# RasPiDV.net
KiCad netlist of a schematic drawn in EAGLE
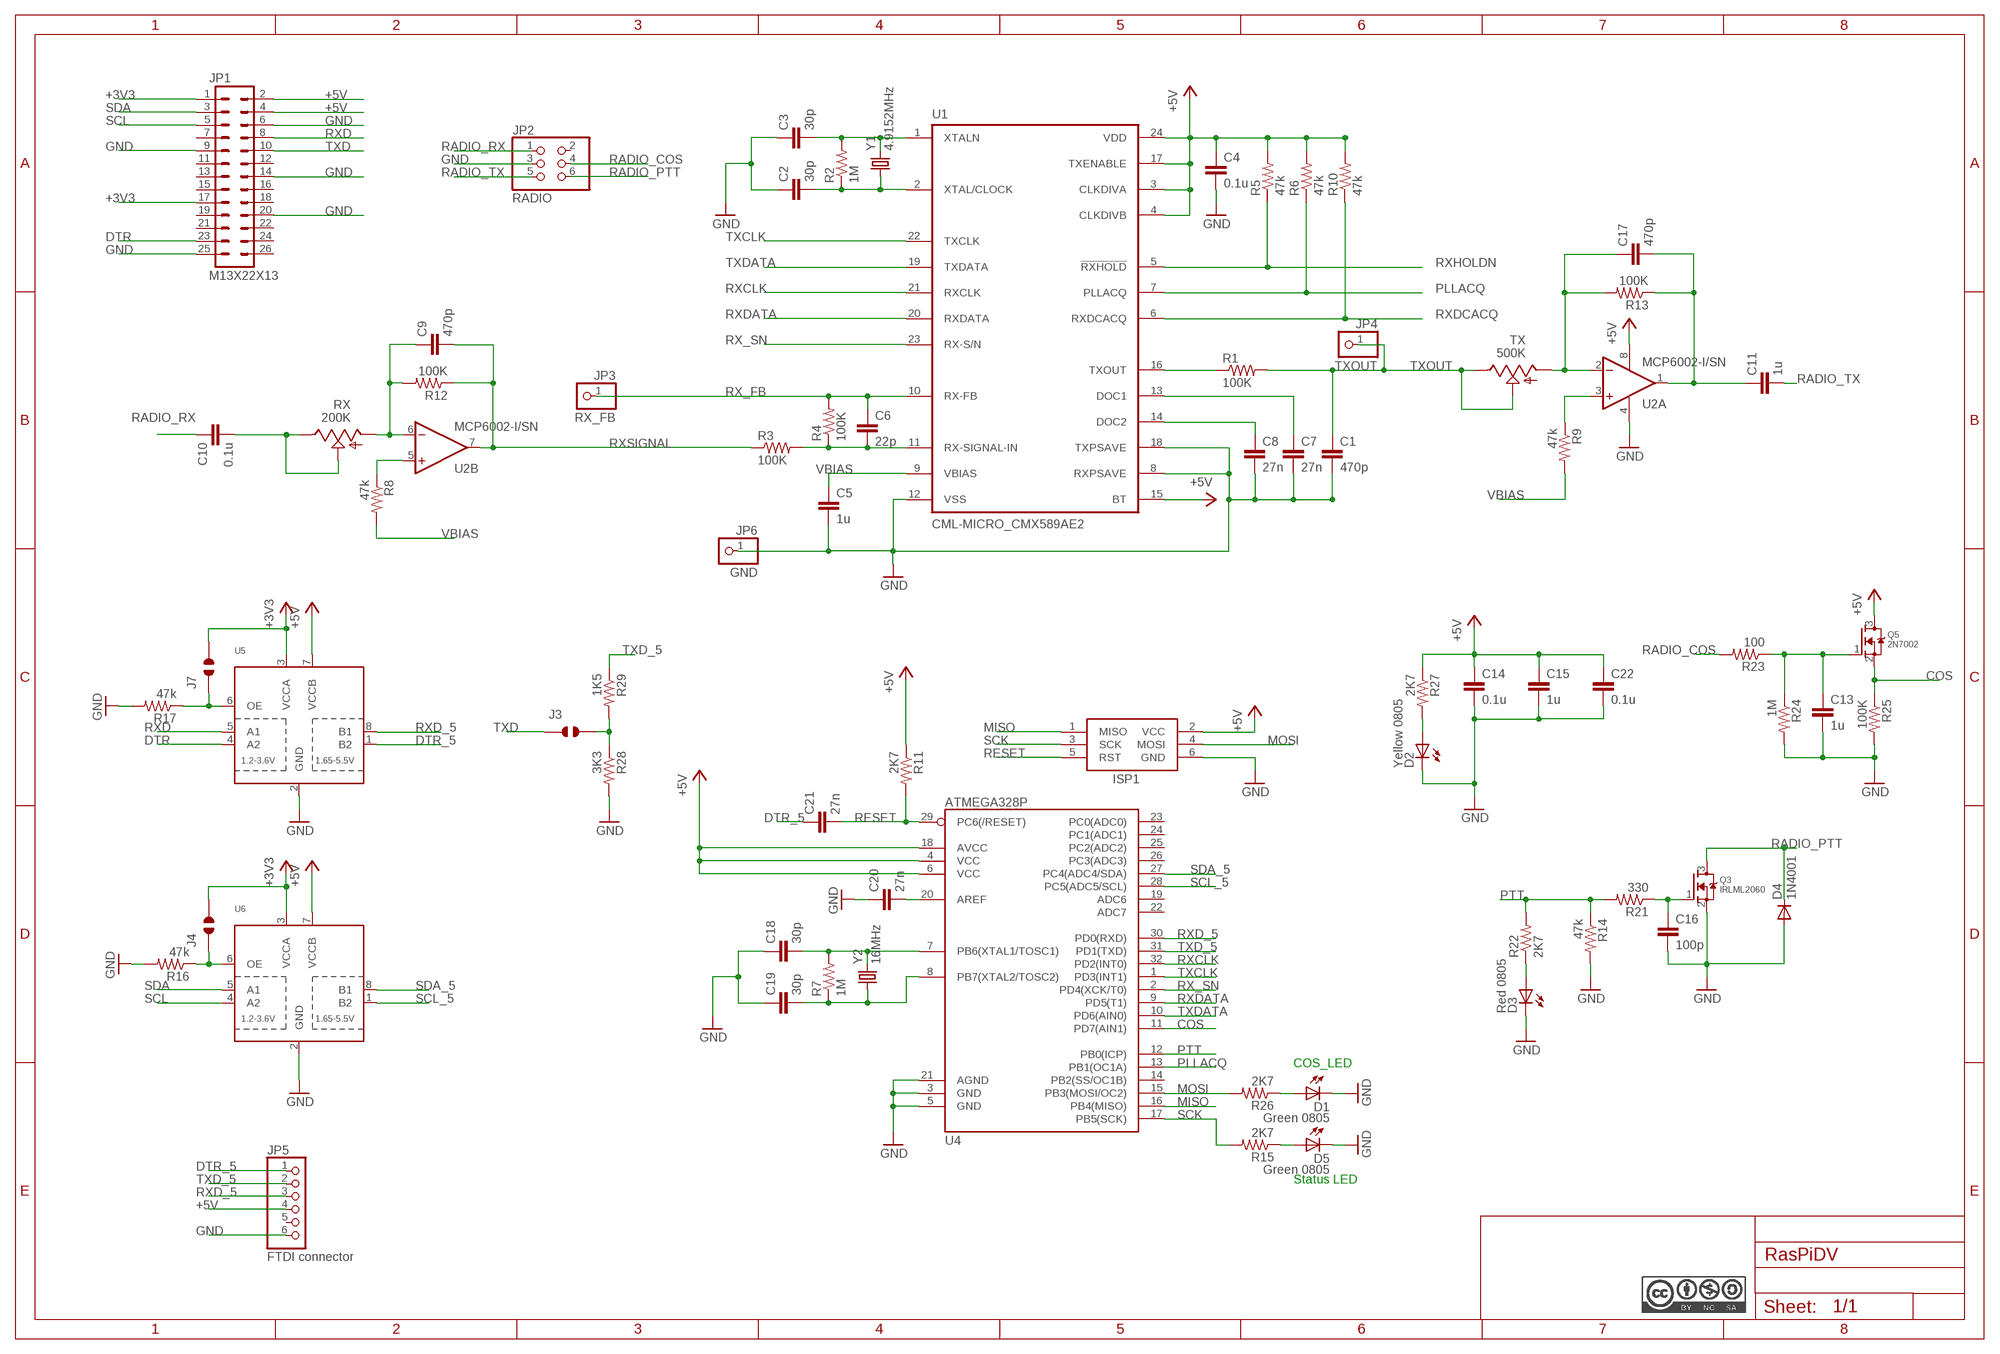
[diagram p0: schematic, sheet 1]

(export (version "E")
  (design (tool "Eeschema 10.0.6"))
  (components
    (comp (ref "C1")
      (value "470p")
      (footprint "eagle-import:C0805")
      (libsource (lib "eagle-import") (part "C-EUC0805"))
    )
    (comp (ref "C2")
      (value "30p")
      (footprint "eagle-import:C0805")
      (libsource (lib "eagle-import") (part "C-EUC0805"))
    )
    (comp (ref "C3")
      (value "30p")
      (footprint "eagle-import:C0805")
      (libsource (lib "eagle-import") (part "C-EUC0805"))
    )
    (comp (ref "C4")
      (value "0.1u")
      (footprint "eagle-import:C0805")
      (libsource (lib "eagle-import") (part "C-EUC0805"))
    )
    (comp (ref "C5")
      (value "1u")
      (footprint "eagle-import:C0805")
      (libsource (lib "eagle-import") (part "C-EUC0805"))
    )
    (comp (ref "C6")
      (value "22p")
      (footprint "eagle-import:C0805")
      (libsource (lib "eagle-import") (part "C-EUC0805"))
    )
    (comp (ref "C7")
      (value "27n")
      (footprint "eagle-import:C0805")
      (libsource (lib "eagle-import") (part "C-EUC0805"))
    )
    (comp (ref "C8")
      (value "27n")
      (footprint "eagle-import:C0805")
      (libsource (lib "eagle-import") (part "C-EUC0805"))
    )
    (comp (ref "C9")
      (value "470p")
      (footprint "eagle-import:C0805")
      (libsource (lib "eagle-import") (part "C-EUC0805"))
    )
    (comp (ref "C10")
      (value "0.1u")
      (footprint "eagle-import:C0805")
      (libsource (lib "eagle-import") (part "C-EUC0805"))
    )
    (comp (ref "C11")
      (value "1u")
      (footprint "eagle-import:C0805")
      (libsource (lib "eagle-import") (part "C-EUC0805"))
    )
    (comp (ref "C13")
      (value "1u")
      (footprint "eagle-import:C0805")
      (libsource (lib "eagle-import") (part "C-EUC0805"))
    )
    (comp (ref "C14")
      (value "0.1u")
      (footprint "eagle-import:C0805")
      (libsource (lib "eagle-import") (part "C-EUC0805"))
    )
    (comp (ref "C15")
      (value "1u")
      (footprint "eagle-import:C0805")
      (libsource (lib "eagle-import") (part "C-EUC0805"))
    )
    (comp (ref "C16")
      (value "100p")
      (footprint "eagle-import:C0805")
      (libsource (lib "eagle-import") (part "C-EUC0805"))
    )
    (comp (ref "C17")
      (value "470p")
      (footprint "eagle-import:C0805")
      (libsource (lib "eagle-import") (part "C-EUC0805"))
    )
    (comp (ref "C18")
      (value "30p")
      (footprint "eagle-import:C0805")
      (libsource (lib "eagle-import") (part "C-EUC0805"))
    )
    (comp (ref "C19")
      (value "30p")
      (footprint "eagle-import:C0805")
      (libsource (lib "eagle-import") (part "C-EUC0805"))
    )
    (comp (ref "C20")
      (value "27n")
      (footprint "eagle-import:C0805")
      (libsource (lib "eagle-import") (part "C-EUC0805"))
    )
    (comp (ref "C21")
      (value "27n")
      (footprint "eagle-import:C0805")
      (libsource (lib "eagle-import") (part "C-EUC0805"))
    )
    (comp (ref "C22")
      (value "0.1u")
      (footprint "eagle-import:C0805")
      (libsource (lib "eagle-import") (part "C-EUC0805"))
    )
    (comp (ref "D1")
      (value "Green 0805")
      (footprint "eagle-import:CHIPLED_0805")
      (libsource (lib "eagle-import") (part "LEDCHIPLED_0805"))
    )
    (comp (ref "D2")
      (value "Yellow 0805")
      (footprint "eagle-import:CHIPLED_0805")
      (libsource (lib "eagle-import") (part "LEDCHIPLED_0805"))
    )
    (comp (ref "D3")
      (value "Red 0805")
      (footprint "eagle-import:CHIPLED_0805")
      (libsource (lib "eagle-import") (part "LEDCHIPLED_0805"))
    )
    (comp (ref "D4")
      (value "1N4001")
      (footprint "eagle-import:MICROMELF-R")
      (libsource (lib "eagle-import") (part "DIODE-MICROMELF-R"))
    )
    (comp (ref "D5")
      (value "Green 0805")
      (footprint "eagle-import:CHIPLED_0805")
      (libsource (lib "eagle-import") (part "LEDCHIPLED_0805"))
    )
    (comp (ref "ISP1")
      (value "AVRISP-6")
      (footprint "eagle-import:AVRISP")
      (libsource (lib "eagle-import") (part "AVRISP-6"))
    )
    (comp (ref "J3")
      (value "JUMPER_SOLDER_1X2")
      (footprint "eagle-import:JUMPER_SOLDER_1X2")
      (libsource (lib "eagle-import") (part "JUMPER_SOLDER_1X2"))
    )
    (comp (ref "J4")
      (value "JUMPER_SOLDER_1X2")
      (footprint "eagle-import:JUMPER_SOLDER_1X2")
      (libsource (lib "eagle-import") (part "JUMPER_SOLDER_1X2"))
    )
    (comp (ref "J7")
      (value "JUMPER_SOLDER_1X2")
      (footprint "eagle-import:JUMPER_SOLDER_1X2")
      (libsource (lib "eagle-import") (part "JUMPER_SOLDER_1X2"))
    )
    (comp (ref "JP1")
      (value "M13X22X13")
      (footprint "eagle-import:2X13")
      (libsource (lib "eagle-import") (part "M13X22X13"))
    )
    (comp (ref "JP2")
      (value "RADIO")
      (footprint "eagle-import:2X03_ROUND_70MIL")
      (libsource (lib "eagle-import") (part "HEADER-2X3"))
    )
    (comp (ref "JP3")
      (value "RX_FB")
      (footprint "eagle-import:1X01_ROUND")
      (libsource (lib "eagle-import") (part "HEADER-1X1ROUND"))
    )
    (comp (ref "JP4")
      (value "TXOUT")
      (footprint "eagle-import:1X01_ROUND")
      (libsource (lib "eagle-import") (part "HEADER-1X1ROUND"))
    )
    (comp (ref "JP5")
      (value "FTDI connector")
      (footprint "eagle-import:1X06-CLEAN")
      (libsource (lib "eagle-import") (part "PINHD-1X6CLEAN"))
    )
    (comp (ref "JP6")
      (value "GND")
      (footprint "eagle-import:1X01_ROUND")
      (libsource (lib "eagle-import") (part "HEADER-1X1ROUND"))
    )
    (comp (ref "Q3")
      (value "IRLML2060")
      (footprint "eagle-import:SOT23")
      (libsource (lib "eagle-import") (part "MOSFET-NREFLOW"))
    )
    (comp (ref "Q5")
      (value "2N7002")
      (footprint "eagle-import:SOT23-R")
      (libsource (lib "eagle-import") (part "microbuilder_MOSFET-NREFLOW"))
    )
    (comp (ref "R1")
      (value "100K")
      (footprint "eagle-import:M0805")
      (libsource (lib "eagle-import") (part "R-US_M0805"))
    )
    (comp (ref "R2")
      (value "1M")
      (footprint "eagle-import:M0805")
      (libsource (lib "eagle-import") (part "R-US_M0805"))
    )
    (comp (ref "R3")
      (value "100K")
      (footprint "eagle-import:M0805")
      (libsource (lib "eagle-import") (part "R-US_M0805"))
    )
    (comp (ref "R4")
      (value "100K")
      (footprint "eagle-import:M0805")
      (libsource (lib "eagle-import") (part "R-US_M0805"))
    )
    (comp (ref "R5")
      (value "47k")
      (footprint "eagle-import:M0805")
      (libsource (lib "eagle-import") (part "R-US_M0805"))
    )
    (comp (ref "R6")
      (value "47k")
      (footprint "eagle-import:M0805")
      (libsource (lib "eagle-import") (part "R-US_M0805"))
    )
    (comp (ref "R7")
      (value "1M")
      (footprint "eagle-import:M0805")
      (libsource (lib "eagle-import") (part "R-US_M0805"))
    )
    (comp (ref "R8")
      (value "47k")
      (footprint "eagle-import:M0805")
      (libsource (lib "eagle-import") (part "R-US_M0805"))
    )
    (comp (ref "R9")
      (value "47k")
      (footprint "eagle-import:M0805")
      (libsource (lib "eagle-import") (part "R-US_M0805"))
    )
    (comp (ref "R10")
      (value "47k")
      (footprint "eagle-import:M0805")
      (libsource (lib "eagle-import") (part "R-US_M0805"))
    )
    (comp (ref "R11")
      (value "2K7")
      (footprint "eagle-import:M0805")
      (libsource (lib "eagle-import") (part "R-US_M0805"))
    )
    (comp (ref "R12")
      (value "100K")
      (footprint "eagle-import:M0805")
      (libsource (lib "eagle-import") (part "R-US_M0805"))
    )
    (comp (ref "R13")
      (value "100K")
      (footprint "eagle-import:M0805")
      (libsource (lib "eagle-import") (part "R-US_M0805"))
    )
    (comp (ref "R14")
      (value "47k")
      (footprint "eagle-import:M0805")
      (libsource (lib "eagle-import") (part "R-US_M0805"))
    )
    (comp (ref "R15")
      (value "2K7")
      (footprint "eagle-import:M0805")
      (libsource (lib "eagle-import") (part "R-US_M0805"))
    )
    (comp (ref "R16")
      (value "47k")
      (footprint "eagle-import:M0805")
      (libsource (lib "eagle-import") (part "R-US_M0805"))
    )
    (comp (ref "R17")
      (value "47k")
      (footprint "eagle-import:M0805")
      (libsource (lib "eagle-import") (part "R-US_M0805"))
    )
    (comp (ref "R21")
      (value "330")
      (footprint "eagle-import:M0805")
      (libsource (lib "eagle-import") (part "R-US_M0805"))
    )
    (comp (ref "R22")
      (value "2K7")
      (footprint "eagle-import:M0805")
      (libsource (lib "eagle-import") (part "R-US_M0805"))
    )
    (comp (ref "R23")
      (value "100")
      (footprint "eagle-import:M0805")
      (libsource (lib "eagle-import") (part "R-US_M0805"))
    )
    (comp (ref "R24")
      (value "1M")
      (footprint "eagle-import:M0805")
      (libsource (lib "eagle-import") (part "R-US_M0805"))
    )
    (comp (ref "R25")
      (value "100K")
      (footprint "eagle-import:M0805")
      (libsource (lib "eagle-import") (part "R-US_M0805"))
    )
    (comp (ref "R26")
      (value "2K7")
      (footprint "eagle-import:M0805")
      (libsource (lib "eagle-import") (part "R-US_M0805"))
    )
    (comp (ref "R27")
      (value "2K7")
      (footprint "eagle-import:M0805")
      (libsource (lib "eagle-import") (part "R-US_M0805"))
    )
    (comp (ref "R28")
      (value "3K3")
      (footprint "eagle-import:M0805")
      (libsource (lib "eagle-import") (part "R-US_M0805"))
    )
    (comp (ref "R29")
      (value "1K5")
      (footprint "eagle-import:M0805")
      (libsource (lib "eagle-import") (part "R-US_M0805"))
    )
    (comp (ref "RX")
      (value "200K")
      (footprint "eagle-import:B25P")
      (libsource (lib "eagle-import") (part "TRIM_US-B25P"))
    )
    (comp (ref "TX")
      (value "500K")
      (footprint "eagle-import:B25P")
      (libsource (lib "eagle-import") (part "TRIM_US-B25P"))
    )
    (comp (ref "U1")
      (value "CML-MICRO_CMX589AE2")
      (footprint "eagle-import:AIS_MK2_CML-MICRO_TSSOP24")
      (libsource (lib "eagle-import") (part "AIS_MK2_CML-MICRO_CMX589AE2"))
    )
    (comp (ref "U2")
      (value "MCP6002-I/SN")
      (footprint "eagle-import:SOIC-8")
      (libsource (lib "eagle-import") (part "MCP6002-I/SN"))
    )
    (comp (ref "U4")
      (value "ATMEGA328P")
      (footprint "eagle-import:TQFP32-08")
      (libsource (lib "eagle-import") (part "ATMEGA328_SMT"))
    )
    (comp (ref "U5")
      (value "TXS0102DCTR")
      (footprint "eagle-import:SO08")
      (libsource (lib "eagle-import") (part "TXS0102DCTR"))
    )
    (comp (ref "U6")
      (value "TXS0102DCTR")
      (footprint "eagle-import:SO08")
      (libsource (lib "eagle-import") (part "TXS0102DCTR"))
    )
    (comp (ref "Y1")
      (value "4.9152MHz")
      (footprint "eagle-import:CRYSTAL_HC49_S")
      (libsource (lib "eagle-import") (part "CRYSTAL_CRYSTALHC49S"))
    )
    (comp (ref "Y2")
      (value "16MHz")
      (footprint "eagle-import:CRYSTAL_HC49_S")
      (libsource (lib "eagle-import") (part "CRYSTAL_CRYSTALHC49S"))
    )
  )
  (nets
    (net (code "1") (name "+3V3") (class "Default")
      (node (ref "J4") (pin "2") (pinfunction "2_2") (pintype "passive"))
      (node (ref "J7") (pin "2") (pinfunction "2_2") (pintype "passive"))
      (node (ref "JP1") (pin "1") (pinfunction "1_1") (pintype "passive"))
      (node (ref "JP1") (pin "17") (pinfunction "17_17") (pintype "passive"))
      (node (ref "U5") (pin "3") (pinfunction "VCCA_3") (pintype "bidirectional"))
      (node (ref "U6") (pin "3") (pinfunction "VCCA_3") (pintype "bidirectional"))
    )
    (net (code "2") (name "+5V") (class "Default")
      (node (ref "C14") (pin "1") (pinfunction "1_1") (pintype "passive"))
      (node (ref "C15") (pin "1") (pinfunction "1_1") (pintype "passive"))
      (node (ref "C22") (pin "1") (pinfunction "1_1") (pintype "passive"))
      (node (ref "C4") (pin "1") (pinfunction "1_1") (pintype "passive"))
      (node (ref "ISP1") (pin "2") (pinfunction "VCC_2") (pintype "power_in"))
      (node (ref "JP1") (pin "2") (pinfunction "2_2") (pintype "passive"))
      (node (ref "JP1") (pin "4") (pinfunction "4_4") (pintype "passive"))
      (node (ref "JP5") (pin "4") (pinfunction "4_4") (pintype "passive"))
      (node (ref "Q5") (pin "3") (pinfunction "D_3") (pintype "bidirectional"))
      (node (ref "R10") (pin "2") (pinfunction "2_2") (pintype "passive"))
      (node (ref "R11") (pin "1") (pinfunction "1_1") (pintype "passive"))
      (node (ref "R27") (pin "1") (pinfunction "1_1") (pintype "passive"))
      (node (ref "R5") (pin "2") (pinfunction "2_2") (pintype "passive"))
      (node (ref "R6") (pin "2") (pinfunction "2_2") (pintype "passive"))
      (node (ref "U1") (pin "15") (pinfunction "BT_15") (pintype "input"))
      (node (ref "U1") (pin "17") (pinfunction "TXENABLE_17") (pintype "input"))
      (node (ref "U1") (pin "24") (pinfunction "VDD_24") (pintype "power_in"))
      (node (ref "U1") (pin "3") (pinfunction "CLKDIVA_3") (pintype "input"))
      (node (ref "U1") (pin "4") (pinfunction "CLKDIVB_4") (pintype "input"))
      (node (ref "U2") (pin "8") (pinfunction "V+_8") (pintype "power_in"))
      (node (ref "U4") (pin "18") (pinfunction "AVCC_18") (pintype "bidirectional"))
      (node (ref "U4") (pin "4") (pinfunction "VCC_4") (pintype "bidirectional"))
      (node (ref "U4") (pin "6") (pinfunction "VCC_6") (pintype "bidirectional"))
      (node (ref "U5") (pin "7") (pinfunction "VCCB_7") (pintype "bidirectional"))
      (node (ref "U6") (pin "7") (pinfunction "VCCB_7") (pintype "bidirectional"))
    )
    (net (code "3") (name "/COS") (class "Default")
      (node (ref "Q5") (pin "2") (pinfunction "S_2") (pintype "bidirectional"))
      (node (ref "R25") (pin "1") (pinfunction "1_1") (pintype "passive"))
      (node (ref "U4") (pin "11") (pinfunction "PD7(AIN1)_11") (pintype "bidirectional"))
    )
    (net (code "4") (name "/DTR") (class "Default")
      (node (ref "JP1") (pin "23") (pinfunction "23_23") (pintype "passive"))
      (node (ref "U5") (pin "4") (pinfunction "A2_4") (pintype "bidirectional"))
    )
    (net (code "5") (name "/DTR_5") (class "Default")
      (node (ref "C21") (pin "1") (pinfunction "1_1") (pintype "passive"))
      (node (ref "JP5") (pin "1") (pinfunction "1_1") (pintype "passive"))
      (node (ref "U5") (pin "1") (pinfunction "B2_1") (pintype "bidirectional"))
    )
    (net (code "6") (name "/MISO") (class "Default")
      (node (ref "ISP1") (pin "1") (pinfunction "MISO_1") (pintype "input"))
      (node (ref "U4") (pin "16") (pinfunction "PB4(MISO)_16") (pintype "bidirectional"))
    )
    (net (code "7") (name "/MOSI") (class "Default")
      (node (ref "ISP1") (pin "4") (pinfunction "MOSI_4") (pintype "output"))
      (node (ref "R26") (pin "2") (pinfunction "2_2") (pintype "passive"))
      (node (ref "U4") (pin "15") (pinfunction "PB3(MOSI/OC2)_15") (pintype "bidirectional"))
    )
    (net (code "8") (name "/PLLACQ") (class "Default")
      (node (ref "R6") (pin "1") (pinfunction "1_1") (pintype "passive"))
      (node (ref "U1") (pin "7") (pinfunction "PLLACQ_7") (pintype "input"))
      (node (ref "U4") (pin "13") (pinfunction "PB1(OC1A)_13") (pintype "bidirectional"))
    )
    (net (code "9") (name "/PTT") (class "Default")
      (node (ref "R14") (pin "1") (pinfunction "1_1") (pintype "passive"))
      (node (ref "R21") (pin "2") (pinfunction "2_2") (pintype "passive"))
      (node (ref "R22") (pin "2") (pinfunction "2_2") (pintype "passive"))
      (node (ref "U4") (pin "12") (pinfunction "PB0(ICP)_12") (pintype "bidirectional"))
    )
    (net (code "10") (name "/RADIO_COS") (class "Default")
      (node (ref "JP2") (pin "4") (pinfunction "4_4") (pintype "passive"))
      (node (ref "R23") (pin "2") (pinfunction "2_2") (pintype "passive"))
    )
    (net (code "11") (name "/RADIO_PTT") (class "Default")
      (node (ref "D4") (pin "C") (pinfunction "C_C") (pintype "passive"))
      (node (ref "JP2") (pin "6") (pinfunction "6_6") (pintype "passive"))
      (node (ref "Q3") (pin "3") (pinfunction "D_3") (pintype "bidirectional"))
    )
    (net (code "12") (name "/RADIO_RX") (class "Default")
      (node (ref "C10") (pin "1") (pinfunction "1_1") (pintype "passive"))
      (node (ref "JP2") (pin "1") (pinfunction "1_1") (pintype "passive"))
    )
    (net (code "13") (name "/RADIO_TX") (class "Default")
      (node (ref "C11") (pin "2") (pinfunction "2_2") (pintype "passive"))
      (node (ref "JP2") (pin "5") (pinfunction "5_5") (pintype "passive"))
    )
    (net (code "14") (name "/RESET") (class "Default")
      (node (ref "C21") (pin "2") (pinfunction "2_2") (pintype "passive"))
      (node (ref "ISP1") (pin "5") (pinfunction "RST_5") (pintype "output"))
      (node (ref "R11") (pin "2") (pinfunction "2_2") (pintype "passive"))
      (node (ref "U4") (pin "29") (pinfunction "PC6(/RESET)_29") (pintype "bidirectional"))
    )
    (net (code "15") (name "/RXCLK") (class "Default")
      (node (ref "U1") (pin "21") (pinfunction "RXCLK_21") (pintype "output"))
      (node (ref "U4") (pin "32") (pinfunction "PD2(INT0)_32") (pintype "bidirectional"))
    )
    (net (code "16") (name "/RXD") (class "Default")
      (node (ref "JP1") (pin "8") (pinfunction "8_8") (pintype "passive"))
      (node (ref "U5") (pin "5") (pinfunction "A1_5") (pintype "bidirectional"))
    )
    (net (code "17") (name "/RXDATA") (class "Default")
      (node (ref "U1") (pin "20") (pinfunction "RXDATA_20") (pintype "output"))
      (node (ref "U4") (pin "9") (pinfunction "PD5(T1)_9") (pintype "bidirectional"))
    )
    (net (code "18") (name "/RXDCACQ") (class "Default")
      (node (ref "R10") (pin "1") (pinfunction "1_1") (pintype "passive"))
      (node (ref "U1") (pin "6") (pinfunction "RXDCACQ_6") (pintype "input"))
    )
    (net (code "19") (name "/RXD_5") (class "Default")
      (node (ref "JP5") (pin "3") (pinfunction "3_3") (pintype "passive"))
      (node (ref "U4") (pin "30") (pinfunction "PD0(RXD)_30") (pintype "bidirectional"))
      (node (ref "U5") (pin "8") (pinfunction "B1_8") (pintype "bidirectional"))
    )
    (net (code "20") (name "/RXHOLDN") (class "Default")
      (node (ref "R5") (pin "1") (pinfunction "1_1") (pintype "passive"))
      (node (ref "U1") (pin "5") (pinfunction "~{RXHOLD}_5") (pintype "input"))
    )
    (net (code "21") (name "/RXSIGNAL") (class "Default")
      (node (ref "C9") (pin "2") (pinfunction "2_2") (pintype "passive"))
      (node (ref "R12") (pin "1") (pinfunction "1_1") (pintype "passive"))
      (node (ref "R3") (pin "1") (pinfunction "1_1") (pintype "passive"))
      (node (ref "U2") (pin "7") (pinfunction "OUT_7") (pintype "output"))
    )
    (net (code "22") (name "/RX_FB") (class "Default")
      (node (ref "C6") (pin "1") (pinfunction "1_1") (pintype "passive"))
      (node (ref "JP3") (pin "1") (pinfunction "1_1") (pintype "passive"))
      (node (ref "R4") (pin "2") (pinfunction "2_2") (pintype "passive"))
      (node (ref "U1") (pin "10") (pinfunction "RX-FB_10") (pintype "input"))
    )
    (net (code "23") (name "/RX_SN") (class "Default")
      (node (ref "U1") (pin "23") (pinfunction "RX-S/N_23") (pintype "output"))
      (node (ref "U4") (pin "2") (pinfunction "PD4(XCK/T0)_2") (pintype "bidirectional"))
    )
    (net (code "24") (name "/SCK") (class "Default")
      (node (ref "ISP1") (pin "3") (pinfunction "SCK_3") (pintype "output"))
      (node (ref "R15") (pin "2") (pinfunction "2_2") (pintype "passive"))
      (node (ref "U4") (pin "17") (pinfunction "PB5(SCK)_17") (pintype "bidirectional"))
    )
    (net (code "25") (name "/SCL") (class "Default")
      (node (ref "JP1") (pin "5") (pinfunction "5_5") (pintype "passive"))
      (node (ref "U6") (pin "4") (pinfunction "A2_4") (pintype "bidirectional"))
    )
    (net (code "26") (name "/SCL_5") (class "Default")
      (node (ref "U4") (pin "28") (pinfunction "PC5(ADC5/SCL)_28") (pintype "bidirectional"))
      (node (ref "U6") (pin "1") (pinfunction "B2_1") (pintype "bidirectional"))
    )
    (net (code "27") (name "/SDA") (class "Default")
      (node (ref "JP1") (pin "3") (pinfunction "3_3") (pintype "passive"))
      (node (ref "U6") (pin "5") (pinfunction "A1_5") (pintype "bidirectional"))
    )
    (net (code "28") (name "/SDA_5") (class "Default")
      (node (ref "U4") (pin "27") (pinfunction "PC4(ADC4/SDA)_27") (pintype "bidirectional"))
      (node (ref "U6") (pin "8") (pinfunction "B1_8") (pintype "bidirectional"))
    )
    (net (code "29") (name "/TXCLK") (class "Default")
      (node (ref "U1") (pin "22") (pinfunction "TXCLK_22") (pintype "output"))
      (node (ref "U4") (pin "1") (pinfunction "PD3(INT1)_1") (pintype "bidirectional"))
    )
    (net (code "30") (name "/TXD") (class "Default")
      (node (ref "J3") (pin "1") (pinfunction "1_1") (pintype "passive"))
      (node (ref "JP1") (pin "10") (pinfunction "10_10") (pintype "passive"))
    )
    (net (code "31") (name "/TXDATA") (class "Default")
      (node (ref "U1") (pin "19") (pinfunction "TXDATA_19") (pintype "input"))
      (node (ref "U4") (pin "10") (pinfunction "PD6(AIN0)_10") (pintype "bidirectional"))
    )
    (net (code "32") (name "/TXD_5") (class "Default")
      (node (ref "JP5") (pin "2") (pinfunction "2_2") (pintype "passive"))
      (node (ref "R29") (pin "1") (pinfunction "1_1") (pintype "passive"))
      (node (ref "U4") (pin "31") (pinfunction "PD1(TXD)_31") (pintype "bidirectional"))
    )
    (net (code "33") (name "/TXOUT") (class "Default")
      (node (ref "C1") (pin "1") (pinfunction "1_1") (pintype "passive"))
      (node (ref "JP4") (pin "1") (pinfunction "1_1") (pintype "passive"))
      (node (ref "R1") (pin "2") (pinfunction "2_2") (pintype "passive"))
      (node (ref "TX") (pin "E") (pinfunction "E_E") (pintype "passive"))
      (node (ref "TX") (pin "S") (pinfunction "S_S") (pintype "passive"))
    )
    (net (code "34") (name "/VBIAS") (class "Default")
      (node (ref "C5") (pin "1") (pinfunction "1_1") (pintype "passive"))
      (node (ref "R8") (pin "2") (pinfunction "2_2") (pintype "passive"))
      (node (ref "R9") (pin "2") (pinfunction "2_2") (pintype "passive"))
      (node (ref "U1") (pin "9") (pinfunction "VBIAS_9") (pintype "input"))
    )
    (net (code "35") (name "GND") (class "Default")
      (node (ref "C1") (pin "2") (pinfunction "2_2") (pintype "passive"))
      (node (ref "C13") (pin "2") (pinfunction "2_2") (pintype "passive"))
      (node (ref "C14") (pin "2") (pinfunction "2_2") (pintype "passive"))
      (node (ref "C15") (pin "2") (pinfunction "2_2") (pintype "passive"))
      (node (ref "C16") (pin "2") (pinfunction "2_2") (pintype "passive"))
      (node (ref "C18") (pin "1") (pinfunction "1_1") (pintype "passive"))
      (node (ref "C19") (pin "1") (pinfunction "1_1") (pintype "passive"))
      (node (ref "C2") (pin "1") (pinfunction "1_1") (pintype "passive"))
      (node (ref "C20") (pin "1") (pinfunction "1_1") (pintype "passive"))
      (node (ref "C22") (pin "2") (pinfunction "2_2") (pintype "passive"))
      (node (ref "C3") (pin "1") (pinfunction "1_1") (pintype "passive"))
      (node (ref "C4") (pin "2") (pinfunction "2_2") (pintype "passive"))
      (node (ref "C5") (pin "2") (pinfunction "2_2") (pintype "passive"))
      (node (ref "C7") (pin "2") (pinfunction "2_2") (pintype "passive"))
      (node (ref "C8") (pin "2") (pinfunction "2_2") (pintype "passive"))
      (node (ref "D1") (pin "C") (pinfunction "C_C") (pintype "passive"))
      (node (ref "D2") (pin "C") (pinfunction "C_C") (pintype "passive"))
      (node (ref "D3") (pin "C") (pinfunction "C_C") (pintype "passive"))
      (node (ref "D4") (pin "A") (pinfunction "A_A") (pintype "passive"))
      (node (ref "D5") (pin "C") (pinfunction "C_C") (pintype "passive"))
      (node (ref "ISP1") (pin "6") (pinfunction "GND_6") (pintype "power_in"))
      (node (ref "JP1") (pin "14") (pinfunction "14_14") (pintype "passive"))
      (node (ref "JP1") (pin "20") (pinfunction "20_20") (pintype "passive"))
      (node (ref "JP1") (pin "25") (pinfunction "25_25") (pintype "passive"))
      (node (ref "JP1") (pin "6") (pinfunction "6_6") (pintype "passive"))
      (node (ref "JP1") (pin "9") (pinfunction "9_9") (pintype "passive"))
      (node (ref "JP2") (pin "3") (pinfunction "3_3") (pintype "passive"))
      (node (ref "JP5") (pin "6") (pinfunction "6_6") (pintype "passive"))
      (node (ref "JP6") (pin "1") (pinfunction "1_1") (pintype "passive"))
      (node (ref "Q3") (pin "2") (pinfunction "S_2") (pintype "bidirectional"))
      (node (ref "R14") (pin "2") (pinfunction "2_2") (pintype "passive"))
      (node (ref "R16") (pin "2") (pinfunction "2_2") (pintype "passive"))
      (node (ref "R17") (pin "2") (pinfunction "2_2") (pintype "passive"))
      (node (ref "R24") (pin "2") (pinfunction "2_2") (pintype "passive"))
      (node (ref "R25") (pin "2") (pinfunction "2_2") (pintype "passive"))
      (node (ref "R28") (pin "2") (pinfunction "2_2") (pintype "passive"))
      (node (ref "U1") (pin "12") (pinfunction "VSS_12") (pintype "power_in"))
      (node (ref "U1") (pin "18") (pinfunction "TXPSAVE_18") (pintype "input"))
      (node (ref "U1") (pin "8") (pinfunction "RXPSAVE_8") (pintype "input"))
      (node (ref "U2") (pin "4") (pinfunction "V-_4") (pintype "power_in"))
      (node (ref "U4") (pin "21") (pinfunction "AGND_21") (pintype "bidirectional"))
      (node (ref "U4") (pin "3") (pinfunction "GND_3") (pintype "bidirectional"))
      (node (ref "U4") (pin "5") (pinfunction "GND_5") (pintype "bidirectional"))
      (node (ref "U5") (pin "2") (pinfunction "GND_2") (pintype "bidirectional"))
      (node (ref "U6") (pin "2") (pinfunction "GND_2") (pintype "bidirectional"))
    )
    (net (code "36") (name "Net-(C10-Pad2)") (class "Default")
      (node (ref "C10") (pin "2") (pinfunction "2_2") (pintype "passive"))
      (node (ref "RX") (pin "E") (pinfunction "E_E") (pintype "passive"))
      (node (ref "RX") (pin "S") (pinfunction "S_S") (pintype "passive"))
    )
    (net (code "37") (name "Net-(D1-PadA)") (class "Default")
      (node (ref "D1") (pin "A") (pinfunction "A_A") (pintype "passive"))
      (node (ref "R26") (pin "1") (pinfunction "1_1") (pintype "passive"))
    )
    (net (code "38") (name "Net-(D2-PadA)") (class "Default")
      (node (ref "D2") (pin "A") (pinfunction "A_A") (pintype "passive"))
      (node (ref "R27") (pin "2") (pinfunction "2_2") (pintype "passive"))
    )
    (net (code "39") (name "Net-(D3-PadA)") (class "Default")
      (node (ref "D3") (pin "A") (pinfunction "A_A") (pintype "passive"))
      (node (ref "R22") (pin "1") (pinfunction "1_1") (pintype "passive"))
    )
    (net (code "40") (name "Net-(D5-PadA)") (class "Default")
      (node (ref "D5") (pin "A") (pinfunction "A_A") (pintype "passive"))
      (node (ref "R15") (pin "1") (pinfunction "1_1") (pintype "passive"))
    )
    (net (code "41") (name "Net-(J3-Pad2)") (class "Default")
      (node (ref "J3") (pin "2") (pinfunction "2_2") (pintype "passive"))
      (node (ref "R28") (pin "1") (pinfunction "1_1") (pintype "passive"))
      (node (ref "R29") (pin "2") (pinfunction "2_2") (pintype "passive"))
    )
    (net (code "42") (name "Net-(Q3-G)") (class "Default")
      (node (ref "C16") (pin "1") (pinfunction "1_1") (pintype "passive"))
      (node (ref "Q3") (pin "1") (pinfunction "G_1") (pintype "bidirectional"))
      (node (ref "R21") (pin "1") (pinfunction "1_1") (pintype "passive"))
    )
    (net (code "43") (name "Net-(Q5-G)") (class "Default")
      (node (ref "C13") (pin "1") (pinfunction "1_1") (pintype "passive"))
      (node (ref "Q5") (pin "1") (pinfunction "G_1") (pintype "bidirectional"))
      (node (ref "R23") (pin "1") (pinfunction "1_1") (pintype "passive"))
      (node (ref "R24") (pin "1") (pinfunction "1_1") (pintype "passive"))
    )
    (net (code "44") (name "Net-(U1-DOC1)") (class "Default")
      (node (ref "C7") (pin "1") (pinfunction "1_1") (pintype "passive"))
      (node (ref "U1") (pin "13") (pinfunction "DOC1_13") (pintype "passive"))
    )
    (net (code "45") (name "Net-(U1-DOC2)") (class "Default")
      (node (ref "C8") (pin "1") (pinfunction "1_1") (pintype "passive"))
      (node (ref "U1") (pin "14") (pinfunction "DOC2_14") (pintype "passive"))
    )
    (net (code "46") (name "Net-(U1-RX-SIGNAL-IN)") (class "Default")
      (node (ref "C6") (pin "2") (pinfunction "2_2") (pintype "passive"))
      (node (ref "R3") (pin "2") (pinfunction "2_2") (pintype "passive"))
      (node (ref "R4") (pin "1") (pinfunction "1_1") (pintype "passive"))
      (node (ref "U1") (pin "11") (pinfunction "RX-SIGNAL-IN_11") (pintype "input"))
    )
    (net (code "47") (name "Net-(U1-TXOUT)") (class "Default")
      (node (ref "R1") (pin "1") (pinfunction "1_1") (pintype "passive"))
      (node (ref "U1") (pin "16") (pinfunction "TXOUT_16") (pintype "output"))
    )
    (net (code "48") (name "Net-(U1-XTALN)") (class "Default")
      (node (ref "C3") (pin "2") (pinfunction "2_2") (pintype "passive"))
      (node (ref "R2") (pin "2") (pinfunction "2_2") (pintype "passive"))
      (node (ref "U1") (pin "1") (pinfunction "XTALN_1") (pintype "output"))
      (node (ref "Y1") (pin "2") (pinfunction "2_2") (pintype "passive"))
    )
    (net (code "49") (name "Net-(U1-XTAL{slash}CLOCK)") (class "Default")
      (node (ref "C2") (pin "2") (pinfunction "2_2") (pintype "passive"))
      (node (ref "R2") (pin "1") (pinfunction "1_1") (pintype "passive"))
      (node (ref "U1") (pin "2") (pinfunction "XTAL/CLOCK_2") (pintype "input"))
      (node (ref "Y1") (pin "1") (pinfunction "1_1") (pintype "passive"))
    )
    (net (code "50") (name "Net-(U2A-IN+)") (class "Default")
      (node (ref "R9") (pin "1") (pinfunction "1_1") (pintype "passive"))
      (node (ref "U2") (pin "3") (pinfunction "IN+_3") (pintype "input"))
    )
    (net (code "51") (name "Net-(U2A-IN-)") (class "Default")
      (node (ref "C17") (pin "1") (pinfunction "1_1") (pintype "passive"))
      (node (ref "R13") (pin "2") (pinfunction "2_2") (pintype "passive"))
      (node (ref "TX") (pin "A") (pinfunction "A_A") (pintype "passive"))
      (node (ref "U2") (pin "2") (pinfunction "IN-_2") (pintype "input"))
    )
    (net (code "52") (name "Net-(U2A-OUT)") (class "Default")
      (node (ref "C11") (pin "1") (pinfunction "1_1") (pintype "passive"))
      (node (ref "C17") (pin "2") (pinfunction "2_2") (pintype "passive"))
      (node (ref "R13") (pin "1") (pinfunction "1_1") (pintype "passive"))
      (node (ref "U2") (pin "1") (pinfunction "OUT_1") (pintype "output"))
    )
    (net (code "53") (name "Net-(U2B-IN+)") (class "Default")
      (node (ref "R8") (pin "1") (pinfunction "1_1") (pintype "passive"))
      (node (ref "U2") (pin "5") (pinfunction "IN+_5") (pintype "input"))
    )
    (net (code "54") (name "Net-(U2B-IN-)") (class "Default")
      (node (ref "C9") (pin "1") (pinfunction "1_1") (pintype "passive"))
      (node (ref "R12") (pin "2") (pinfunction "2_2") (pintype "passive"))
      (node (ref "RX") (pin "A") (pinfunction "A_A") (pintype "passive"))
      (node (ref "U2") (pin "6") (pinfunction "IN-_6") (pintype "input"))
    )
    (net (code "55") (name "Net-(U4-AREF)") (class "Default")
      (node (ref "C20") (pin "2") (pinfunction "2_2") (pintype "passive"))
      (node (ref "U4") (pin "20") (pinfunction "AREF_20") (pintype "bidirectional"))
    )
    (net (code "56") (name "Net-(U4-PB6(XTAL1{slash}TOSC1))") (class "Default")
      (node (ref "C18") (pin "2") (pinfunction "2_2") (pintype "passive"))
      (node (ref "R7") (pin "2") (pinfunction "2_2") (pintype "passive"))
      (node (ref "U4") (pin "7") (pinfunction "PB6(XTAL1/TOSC1)_7") (pintype "bidirectional"))
      (node (ref "Y2") (pin "2") (pinfunction "2_2") (pintype "passive"))
    )
    (net (code "57") (name "Net-(U4-PB7(XTAL2{slash}TOSC2))") (class "Default")
      (node (ref "C19") (pin "2") (pinfunction "2_2") (pintype "passive"))
      (node (ref "R7") (pin "1") (pinfunction "1_1") (pintype "passive"))
      (node (ref "U4") (pin "8") (pinfunction "PB7(XTAL2/TOSC2)_8") (pintype "bidirectional"))
      (node (ref "Y2") (pin "1") (pinfunction "1_1") (pintype "passive"))
    )
    (net (code "58") (name "Net-(U5-OE)") (class "Default")
      (node (ref "J7") (pin "1") (pinfunction "1_1") (pintype "passive"))
      (node (ref "R17") (pin "1") (pinfunction "1_1") (pintype "passive"))
      (node (ref "U5") (pin "6") (pinfunction "OE_6") (pintype "bidirectional"))
    )
    (net (code "59") (name "Net-(U6-OE)") (class "Default")
      (node (ref "J4") (pin "1") (pinfunction "1_1") (pintype "passive"))
      (node (ref "R16") (pin "1") (pinfunction "1_1") (pintype "passive"))
      (node (ref "U6") (pin "6") (pinfunction "OE_6") (pintype "bidirectional"))
    )
    (net (code "60") (name "unconnected-(JP1-Pad7)") (class "Default")
      (node (ref "JP1") (pin "7") (pinfunction "7_7") (pintype "passive"))
    )
    (net (code "61") (name "unconnected-(JP1-Pad11)") (class "Default")
      (node (ref "JP1") (pin "11") (pinfunction "11_11") (pintype "passive"))
    )
    (net (code "62") (name "unconnected-(JP1-Pad12)") (class "Default")
      (node (ref "JP1") (pin "12") (pinfunction "12_12") (pintype "passive"))
    )
    (net (code "63") (name "unconnected-(JP1-Pad13)") (class "Default")
      (node (ref "JP1") (pin "13") (pinfunction "13_13") (pintype "passive"))
    )
    (net (code "64") (name "unconnected-(JP1-Pad15)") (class "Default")
      (node (ref "JP1") (pin "15") (pinfunction "15_15") (pintype "passive"))
    )
    (net (code "65") (name "unconnected-(JP1-Pad16)") (class "Default")
      (node (ref "JP1") (pin "16") (pinfunction "16_16") (pintype "passive"))
    )
    (net (code "66") (name "unconnected-(JP1-Pad18)") (class "Default")
      (node (ref "JP1") (pin "18") (pinfunction "18_18") (pintype "passive"))
    )
    (net (code "67") (name "unconnected-(JP1-Pad19)") (class "Default")
      (node (ref "JP1") (pin "19") (pinfunction "19_19") (pintype "passive"))
    )
    (net (code "68") (name "unconnected-(JP1-Pad21)") (class "Default")
      (node (ref "JP1") (pin "21") (pinfunction "21_21") (pintype "passive"))
    )
    (net (code "69") (name "unconnected-(JP1-Pad22)") (class "Default")
      (node (ref "JP1") (pin "22") (pinfunction "22_22") (pintype "passive"))
    )
    (net (code "70") (name "unconnected-(JP1-Pad24)") (class "Default")
      (node (ref "JP1") (pin "24") (pinfunction "24_24") (pintype "passive"))
    )
    (net (code "71") (name "unconnected-(JP1-Pad26)") (class "Default")
      (node (ref "JP1") (pin "26") (pinfunction "26_26") (pintype "passive"))
    )
    (net (code "72") (name "unconnected-(JP2-Pad2)") (class "Default")
      (node (ref "JP2") (pin "2") (pinfunction "2_2") (pintype "passive"))
    )
    (net (code "73") (name "unconnected-(JP5-Pad5)") (class "Default")
      (node (ref "JP5") (pin "5") (pinfunction "5_5") (pintype "passive"))
    )
    (net (code "74") (name "unconnected-(U4-ADC6-Pad19)") (class "Default")
      (node (ref "U4") (pin "19") (pinfunction "ADC6_19") (pintype "bidirectional"))
    )
    (net (code "75") (name "unconnected-(U4-ADC7-Pad22)") (class "Default")
      (node (ref "U4") (pin "22") (pinfunction "ADC7_22") (pintype "bidirectional"))
    )
    (net (code "76") (name "unconnected-(U4-PB2(SS{slash}OC1B)-Pad14)") (class "Default")
      (node (ref "U4") (pin "14") (pinfunction "PB2(SS/OC1B)_14") (pintype "bidirectional"))
    )
    (net (code "77") (name "unconnected-(U4-PC0(ADC0)-Pad23)") (class "Default")
      (node (ref "U4") (pin "23") (pinfunction "PC0(ADC0)_23") (pintype "bidirectional"))
    )
    (net (code "78") (name "unconnected-(U4-PC1(ADC1)-Pad24)") (class "Default")
      (node (ref "U4") (pin "24") (pinfunction "PC1(ADC1)_24") (pintype "bidirectional"))
    )
    (net (code "79") (name "unconnected-(U4-PC2(ADC2)-Pad25)") (class "Default")
      (node (ref "U4") (pin "25") (pinfunction "PC2(ADC2)_25") (pintype "bidirectional"))
    )
    (net (code "80") (name "unconnected-(U4-PC3(ADC3)-Pad26)") (class "Default")
      (node (ref "U4") (pin "26") (pinfunction "PC3(ADC3)_26") (pintype "bidirectional"))
    )
  )
)
